# ADC.net
KiCad netlist of a schematic drawn in Altium Designer
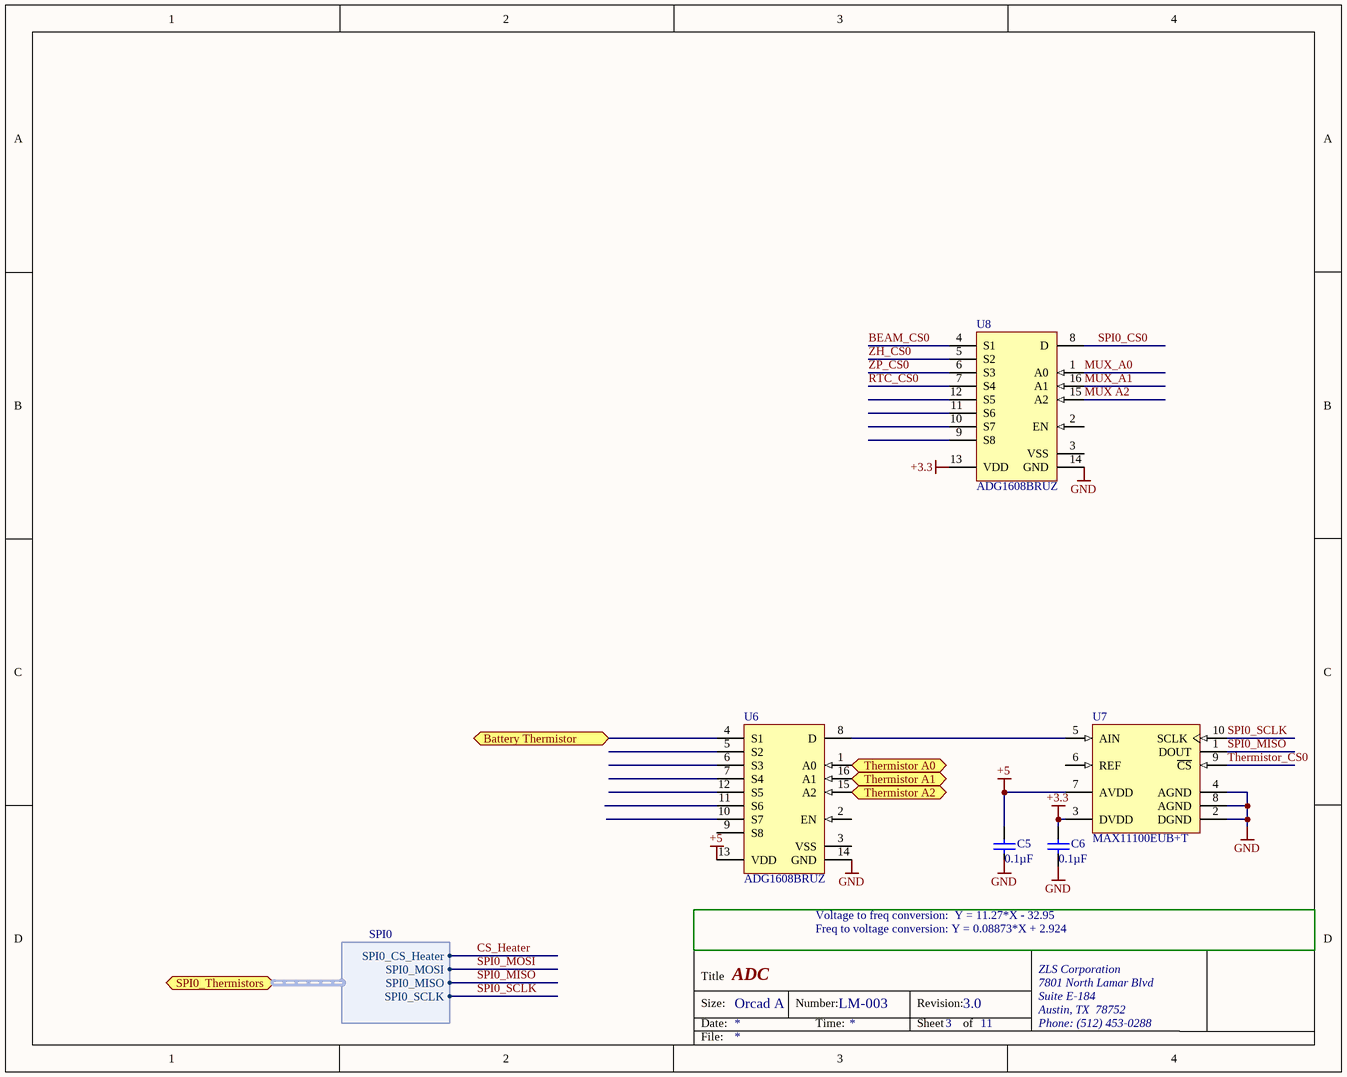
[diagram p0: ADC.SchDoc]

(export (version "E")
  (design (tool "Eeschema 10.0.6"))
  (components
    (comp (ref "C5")
      (value "CAP CER 0.1UF 25V X7R 0805")
      (footprint "CAPC0805(2012)145_N")
      (fields
        (field (name "MANUFACTURER") "Murata Electronics North America")
        (field (name "MANUFACTURER PART NUMBER") "GRM21BR71E104KA01L")
        (field (name "CAPACITANCE") "0.1µF")
        (field (name "TOLERANCE") "±10%")
      )
      (libsource (lib "Altium Content Vault") (part "CMP-1036-04795-1"))
    )
    (comp (ref "C6")
      (value "CAP CER 0.1UF 25V X7R 0805")
      (footprint "CAPC0805(2012)145_N")
      (fields
        (field (name "MANUFACTURER") "Murata Electronics North America")
        (field (name "MANUFACTURER PART NUMBER") "GRM21BR71E104KA01L")
        (field (name "CAPACITANCE") "0.1µF")
        (field (name "TOLERANCE") "±10%")
      )
      (libsource (lib "Altium Content Vault") (part "CMP-1036-04795-1"))
    )
    (comp (ref "U6")
      (value "ADG1608BRUZ")
      (footprint "ADI-RU-16_M")
      (description "4.5 Ohm Ron, 8-Channel +/-5 V,+12 V, +5 V and +3.3 V Multiplexer, 16-pin SOP (RU-16), Tube")
      (fields (field (name "MANUFACTURER") "Analog Devices"))
      (libsource (lib "Altium Content Vault") (part "ADI-ADG1608-RU-16"))
    )
    (comp (ref "U7")
      (value "MAX11100EUB+T")
      (footprint "U10+2_L")
      (description "16-Bit, +5V, 200ksps ADC with 10uA Shutdown, 10-Pin uMAX, -40°C to +85°C, Pb-Free, Tape and Reel")
      (libsource (lib "Altium Content Vault") (part "CON-ADC-MAX11100-IL10"))
    )
    (comp (ref "U8")
      (value "ADG1608BRUZ")
      (footprint "ADI-RU-16_M")
      (description "4.5 Ohm Ron, 8-Channel +/-5 V,+12 V, +5 V and +3.3 V Multiplexer, 16-pin SOP (RU-16), Tube")
      (fields (field (name "MANUFACTURER") "Analog Devices"))
      (libsource (lib "Altium Content Vault") (part "ADI-ADG1608-RU-16"))
    )
  )
  (nets
    (net (code "2") (name "+3.3") (class "Default")
      (node (ref "C6") (pin "1") (pinfunction "1_1") (pintype "passive"))
      (node (ref "U7") (pin "3") (pinfunction "DVDD_3") (pintype "power_in"))
      (node (ref "U8") (pin "13") (pinfunction "VDD_13") (pintype "power_in"))
    )
    (net (code "3") (name "+5") (class "Default")
      (node (ref "C5") (pin "1") (pinfunction "1_1") (pintype "passive"))
      (node (ref "U6") (pin "13") (pinfunction "VDD_13") (pintype "power_in"))
      (node (ref "U7") (pin "7") (pinfunction "AVDD_7") (pintype "power_in"))
    )
    (net (code "4") (name "/BEAM_CS0") (class "Default")
      (node (ref "U8") (pin "4") (pinfunction "S1_4") (pintype "passive"))
    )
    (net (code "5") (name "/Battery Thermistor") (class "Default")
      (node (ref "U6") (pin "4") (pinfunction "S1_4") (pintype "passive"))
    )
    (net (code "7") (name "/MUX A2") (class "Default")
      (node (ref "U8") (pin "15") (pinfunction "A2_15") (pintype "input"))
    )
    (net (code "8") (name "/MUX_A0") (class "Default")
      (node (ref "U8") (pin "1") (pinfunction "A0_1") (pintype "input"))
    )
    (net (code "9") (name "/MUX_A1") (class "Default")
      (node (ref "U8") (pin "16") (pinfunction "A1_16") (pintype "input"))
    )
    (net (code "10") (name "/RTC_CS0") (class "Default")
      (node (ref "U8") (pin "7") (pinfunction "S4_7") (pintype "passive"))
    )
    (net (code "11") (name "/SPI0_CS0") (class "Default")
      (node (ref "U8") (pin "8") (pinfunction "D_8") (pintype "passive"))
    )
    (net (code "12") (name "/SPI0_MISO") (class "Default")
      (node (ref "U7") (pin "1") (pinfunction "DOUT_1") (pintype "tri_state"))
    )
    (net (code "14") (name "/SPI0_SCLK") (class "Default")
      (node (ref "U7") (pin "10") (pinfunction "SCLK_10") (pintype "input"))
    )
    (net (code "15") (name "/Thermistor A0") (class "Default")
      (node (ref "U6") (pin "1") (pinfunction "A0_1") (pintype "input"))
    )
    (net (code "16") (name "/Thermistor A1") (class "Default")
      (node (ref "U6") (pin "16") (pinfunction "A1_16") (pintype "input"))
    )
    (net (code "17") (name "/Thermistor A2") (class "Default")
      (node (ref "U6") (pin "15") (pinfunction "A2_15") (pintype "input"))
    )
    (net (code "18") (name "/Thermistor_CS0") (class "Default")
      (node (ref "U7") (pin "9") (pinfunction "~{CS}_9") (pintype "input"))
    )
    (net (code "19") (name "/ZH_CS0") (class "Default")
      (node (ref "U8") (pin "5") (pinfunction "S2_5") (pintype "passive"))
    )
    (net (code "20") (name "/ZP_CS0") (class "Default")
      (node (ref "U8") (pin "6") (pinfunction "S3_6") (pintype "passive"))
    )
    (net (code "22") (name "GND") (class "Default")
      (node (ref "C6") (pin "2") (pinfunction "2_2") (pintype "passive"))
      (node (ref "U6") (pin "14") (pinfunction "GND_14") (pintype "power_in"))
      (node (ref "U7") (pin "2") (pinfunction "DGND_2") (pintype "power_in"))
      (node (ref "U7") (pin "4") (pinfunction "AGND_4") (pintype "power_in"))
      (node (ref "U7") (pin "8") (pinfunction "AGND_8") (pintype "power_in"))
      (node (ref "U8") (pin "14") (pinfunction "GND_14") (pintype "power_in"))
    )
    (net (code "23") (name "Net-(U6-D)") (class "Default")
      (node (ref "U6") (pin "8") (pinfunction "D_8") (pintype "passive"))
      (node (ref "U7") (pin "5") (pinfunction "AIN_5") (pintype "input"))
    )
    (net (code "24") (name "unconnected-(C5-Pad2)") (class "Default")
      (node (ref "C5") (pin "2") (pinfunction "2_2") (pintype "passive"))
    )
    (net (code "25") (name "unconnected-(U6-EN-Pad2)") (class "Default")
      (node (ref "U6") (pin "2") (pinfunction "EN_2") (pintype "input"))
    )
    (net (code "26") (name "unconnected-(U6-S2-Pad5)") (class "Default")
      (node (ref "U6") (pin "5") (pinfunction "S2_5") (pintype "passive"))
    )
    (net (code "27") (name "unconnected-(U6-S3-Pad6)") (class "Default")
      (node (ref "U6") (pin "6") (pinfunction "S3_6") (pintype "passive"))
    )
    (net (code "28") (name "unconnected-(U6-S4-Pad7)") (class "Default")
      (node (ref "U6") (pin "7") (pinfunction "S4_7") (pintype "passive"))
    )
    (net (code "29") (name "unconnected-(U6-S5-Pad12)") (class "Default")
      (node (ref "U6") (pin "12") (pinfunction "S5_12") (pintype "passive"))
    )
    (net (code "30") (name "unconnected-(U6-S6-Pad11)") (class "Default")
      (node (ref "U6") (pin "11") (pinfunction "S6_11") (pintype "passive"))
    )
    (net (code "31") (name "unconnected-(U6-S7-Pad10)") (class "Default")
      (node (ref "U6") (pin "10") (pinfunction "S7_10") (pintype "passive"))
    )
    (net (code "32") (name "unconnected-(U6-S8-Pad9)") (class "Default")
      (node (ref "U6") (pin "9") (pinfunction "S8_9") (pintype "passive"))
    )
    (net (code "33") (name "unconnected-(U6-VSS-Pad3)") (class "Default")
      (node (ref "U6") (pin "3") (pinfunction "VSS_3") (pintype "power_in"))
    )
    (net (code "34") (name "unconnected-(U7-REF-Pad6)") (class "Default")
      (node (ref "U7") (pin "6") (pinfunction "REF_6") (pintype "input"))
    )
    (net (code "35") (name "unconnected-(U8-EN-Pad2)") (class "Default")
      (node (ref "U8") (pin "2") (pinfunction "EN_2") (pintype "input"))
    )
    (net (code "36") (name "unconnected-(U8-S5-Pad12)") (class "Default")
      (node (ref "U8") (pin "12") (pinfunction "S5_12") (pintype "passive"))
    )
    (net (code "37") (name "unconnected-(U8-S6-Pad11)") (class "Default")
      (node (ref "U8") (pin "11") (pinfunction "S6_11") (pintype "passive"))
    )
    (net (code "38") (name "unconnected-(U8-S7-Pad10)") (class "Default")
      (node (ref "U8") (pin "10") (pinfunction "S7_10") (pintype "passive"))
    )
    (net (code "39") (name "unconnected-(U8-S8-Pad9)") (class "Default")
      (node (ref "U8") (pin "9") (pinfunction "S8_9") (pintype "passive"))
    )
    (net (code "40") (name "unconnected-(U8-VSS-Pad3)") (class "Default")
      (node (ref "U8") (pin "3") (pinfunction "VSS_3") (pintype "power_in"))
    )
  )
)
